# KN-CON_LCD_80.net
KiCad netlist of a schematic drawn in EAGLE
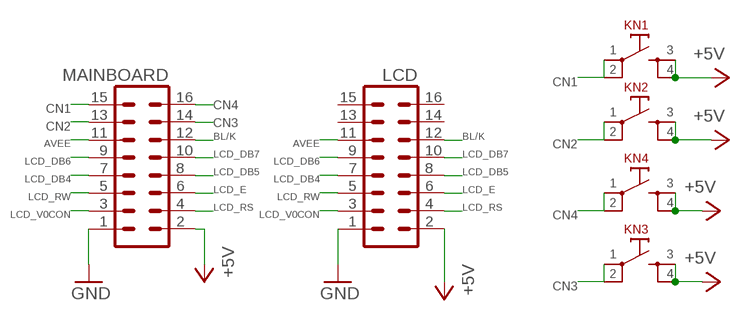
[diagram p0: schematic, sheet 1]

(export (version "E")
  (design (tool "Eeschema 10.0.6"))
  (components
    (comp (ref "KN1")
      (value "LZQ-KN")
      (footprint "eagle-import:LZQ-KN")
      (libsource (lib "eagle-import") (part "LZQ-KN"))
    )
    (comp (ref "KN2")
      (value "LZQ-KN")
      (footprint "eagle-import:LZQ-KN")
      (libsource (lib "eagle-import") (part "LZQ-KN"))
    )
    (comp (ref "KN3")
      (value "LZQ-KN")
      (footprint "eagle-import:LZQ-KN")
      (libsource (lib "eagle-import") (part "LZQ-KN"))
    )
    (comp (ref "KN4")
      (value "LZQ-KN")
      (footprint "eagle-import:LZQ-KN")
      (libsource (lib "eagle-import") (part "LZQ-KN"))
    )
    (comp (ref "LCD")
      (value "ML16")
      (footprint "eagle-import:ML16")
      (fields (field (name "OC_FARNELL") "unknown") (field (name "OC_NEWARK") "unknown"))
      (libsource (lib "eagle-import") (part "ML16"))
    )
    (comp (ref "MAINBOARD")
      (value "ML16")
      (footprint "eagle-import:ML16")
      (fields (field (name "OC_FARNELL") "unknown") (field (name "OC_NEWARK") "unknown"))
      (libsource (lib "eagle-import") (part "ML16"))
    )
  )
  (nets
    (net (code "1") (name "+5V") (class "Default")
      (node (ref "KN1") (pin "3") (pinfunction "3_3") (pintype "bidirectional"))
      (node (ref "KN1") (pin "4") (pinfunction "4_4") (pintype "bidirectional"))
      (node (ref "KN2") (pin "3") (pinfunction "3_3") (pintype "bidirectional"))
      (node (ref "KN2") (pin "4") (pinfunction "4_4") (pintype "bidirectional"))
      (node (ref "KN3") (pin "3") (pinfunction "3_3") (pintype "bidirectional"))
      (node (ref "KN3") (pin "4") (pinfunction "4_4") (pintype "bidirectional"))
      (node (ref "KN4") (pin "3") (pinfunction "3_3") (pintype "bidirectional"))
      (node (ref "KN4") (pin "4") (pinfunction "4_4") (pintype "bidirectional"))
      (node (ref "LCD") (pin "2") (pinfunction "2_2") (pintype "passive"))
      (node (ref "MAINBOARD") (pin "2") (pinfunction "2_2") (pintype "passive"))
    )
    (net (code "2") (name "/AVEE") (class "Default")
      (node (ref "LCD") (pin "11") (pinfunction "11_11") (pintype "passive"))
      (node (ref "MAINBOARD") (pin "11") (pinfunction "11_11") (pintype "passive"))
    )
    (net (code "3") (name "/BL{slash}K") (class "Default")
      (node (ref "LCD") (pin "12") (pinfunction "12_12") (pintype "passive"))
      (node (ref "MAINBOARD") (pin "12") (pinfunction "12_12") (pintype "passive"))
    )
    (net (code "4") (name "/CN1") (class "Default")
      (node (ref "KN1") (pin "1") (pinfunction "1_1") (pintype "bidirectional"))
      (node (ref "KN1") (pin "2") (pinfunction "2_2") (pintype "bidirectional"))
      (node (ref "MAINBOARD") (pin "15") (pinfunction "15_15") (pintype "passive"))
    )
    (net (code "5") (name "/CN2") (class "Default")
      (node (ref "KN2") (pin "1") (pinfunction "1_1") (pintype "bidirectional"))
      (node (ref "KN2") (pin "2") (pinfunction "2_2") (pintype "bidirectional"))
      (node (ref "MAINBOARD") (pin "13") (pinfunction "13_13") (pintype "passive"))
    )
    (net (code "6") (name "/CN3") (class "Default")
      (node (ref "KN3") (pin "1") (pinfunction "1_1") (pintype "bidirectional"))
      (node (ref "KN3") (pin "2") (pinfunction "2_2") (pintype "bidirectional"))
      (node (ref "MAINBOARD") (pin "14") (pinfunction "14_14") (pintype "passive"))
    )
    (net (code "7") (name "/CN4") (class "Default")
      (node (ref "KN4") (pin "1") (pinfunction "1_1") (pintype "bidirectional"))
      (node (ref "KN4") (pin "2") (pinfunction "2_2") (pintype "bidirectional"))
      (node (ref "MAINBOARD") (pin "16") (pinfunction "16_16") (pintype "passive"))
    )
    (net (code "8") (name "/LCD_DB4") (class "Default")
      (node (ref "LCD") (pin "7") (pinfunction "7_7") (pintype "passive"))
      (node (ref "MAINBOARD") (pin "7") (pinfunction "7_7") (pintype "passive"))
    )
    (net (code "9") (name "/LCD_DB5") (class "Default")
      (node (ref "LCD") (pin "8") (pinfunction "8_8") (pintype "passive"))
      (node (ref "MAINBOARD") (pin "8") (pinfunction "8_8") (pintype "passive"))
    )
    (net (code "10") (name "/LCD_DB6") (class "Default")
      (node (ref "LCD") (pin "9") (pinfunction "9_9") (pintype "passive"))
      (node (ref "MAINBOARD") (pin "9") (pinfunction "9_9") (pintype "passive"))
    )
    (net (code "11") (name "/LCD_DB7") (class "Default")
      (node (ref "LCD") (pin "10") (pinfunction "10_10") (pintype "passive"))
      (node (ref "MAINBOARD") (pin "10") (pinfunction "10_10") (pintype "passive"))
    )
    (net (code "12") (name "/LCD_E") (class "Default")
      (node (ref "LCD") (pin "6") (pinfunction "6_6") (pintype "passive"))
      (node (ref "MAINBOARD") (pin "6") (pinfunction "6_6") (pintype "passive"))
    )
    (net (code "13") (name "/LCD_RS") (class "Default")
      (node (ref "LCD") (pin "4") (pinfunction "4_4") (pintype "passive"))
      (node (ref "MAINBOARD") (pin "4") (pinfunction "4_4") (pintype "passive"))
    )
    (net (code "14") (name "/LCD_RW") (class "Default")
      (node (ref "LCD") (pin "5") (pinfunction "5_5") (pintype "passive"))
      (node (ref "MAINBOARD") (pin "5") (pinfunction "5_5") (pintype "passive"))
    )
    (net (code "15") (name "/LCD_V0CON") (class "Default")
      (node (ref "LCD") (pin "3") (pinfunction "3_3") (pintype "passive"))
      (node (ref "MAINBOARD") (pin "3") (pinfunction "3_3") (pintype "passive"))
    )
    (net (code "16") (name "GND") (class "Default")
      (node (ref "LCD") (pin "1") (pinfunction "1_1") (pintype "passive"))
      (node (ref "MAINBOARD") (pin "1") (pinfunction "1_1") (pintype "passive"))
    )
    (net (code "17") (name "unconnected-(LCD-Pad13)") (class "Default")
      (node (ref "LCD") (pin "13") (pinfunction "13_13") (pintype "passive"))
    )
    (net (code "18") (name "unconnected-(LCD-Pad14)") (class "Default")
      (node (ref "LCD") (pin "14") (pinfunction "14_14") (pintype "passive"))
    )
    (net (code "19") (name "unconnected-(LCD-Pad15)") (class "Default")
      (node (ref "LCD") (pin "15") (pinfunction "15_15") (pintype "passive"))
    )
    (net (code "20") (name "unconnected-(LCD-Pad16)") (class "Default")
      (node (ref "LCD") (pin "16") (pinfunction "16_16") (pintype "passive"))
    )
  )
)
